# MCU.net
KiCad netlist of a schematic drawn in Altium Designer
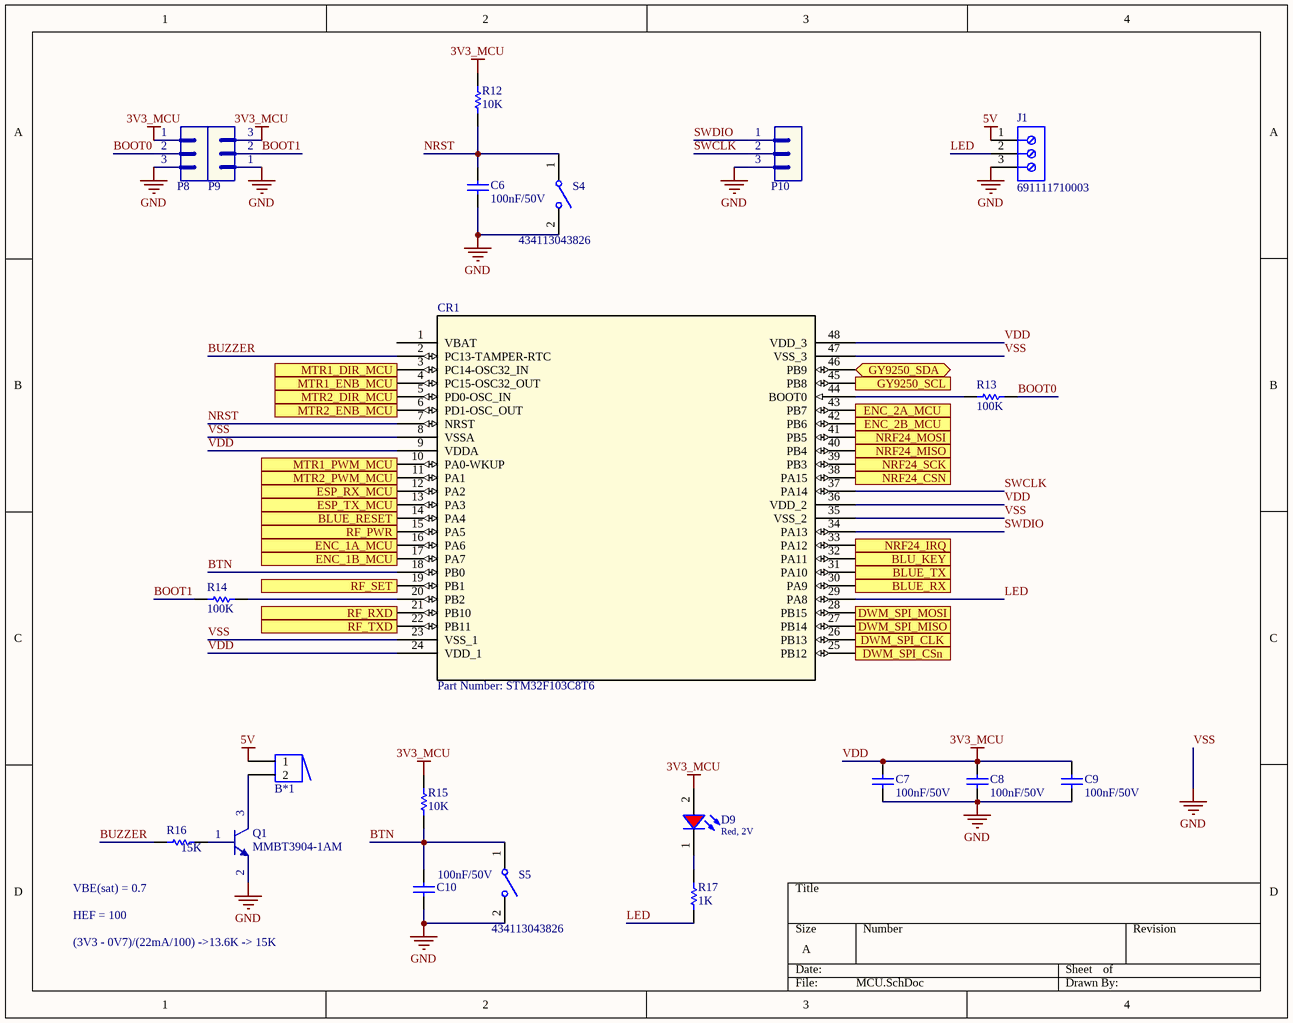
[diagram p0: MCU.SchDoc]

(export (version "E")
  (design (tool "Eeschema 10.0.6"))
  (components
    (comp (ref "B*1") (value "Buzzer") (footprint "BUZZER") (libsource (lib "chicken") (part "Buzzer")))
    (comp (ref "C6")
      (value "100nF/50V")
      (footprint "CAP-SM-0805")
      (description "CAP CER 0.1UF 50V Y5V 0805")
      (fields
        (field (name "MANUFACTURER") "Samsung Electro-Mechanics")
        (field (name "MANUFACTURER PART NUMBER") "CL21F104ZBCNNNC")
      )
      (libsource (lib "Capacitor") (part "Cap-100nF-50V-0805"))
    )
    (comp (ref "C7")
      (value "100nF/50V")
      (footprint "CAP-SM-0805")
      (description "CAP CER 0.1UF 50V Y5V 0805")
      (fields
        (field (name "MANUFACTURER") "Samsung Electro-Mechanics")
        (field (name "MANUFACTURER PART NUMBER") "CL21F104ZBCNNNC")
      )
      (libsource (lib "Capacitor") (part "Cap-100nF-50V-0805"))
    )
    (comp (ref "C8")
      (value "100nF/50V")
      (footprint "CAP-SM-0805")
      (description "CAP CER 0.1UF 50V Y5V 0805")
      (fields
        (field (name "MANUFACTURER") "Samsung Electro-Mechanics")
        (field (name "MANUFACTURER PART NUMBER") "CL21F104ZBCNNNC")
      )
      (libsource (lib "Capacitor") (part "Cap-100nF-50V-0805"))
    )
    (comp (ref "C9")
      (value "100nF/50V")
      (footprint "CAP-SM-0805")
      (description "CAP CER 0.1UF 50V Y5V 0805")
      (fields
        (field (name "MANUFACTURER") "Samsung Electro-Mechanics")
        (field (name "MANUFACTURER PART NUMBER") "CL21F104ZBCNNNC")
      )
      (libsource (lib "Capacitor") (part "Cap-100nF-50V-0805"))
    )
    (comp (ref "C10")
      (value "100nF/50V")
      (footprint "CAP-SM-0805")
      (description "CAP CER 0.1UF 50V Y5V 0805")
      (fields
        (field (name "MANUFACTURER") "Samsung Electro-Mechanics")
        (field (name "MANUFACTURER PART NUMBER") "CL21F104ZBCNNNC")
      )
      (libsource (lib "Capacitor") (part "Cap-100nF-50V-0805"))
    )
    (comp (ref "CR1")
      (value "Part Number: STM32F103C8T6")
      (footprint "LQFP-48")
      (description "No Description Available")
      (fields
        (field (name "MANUFACTURER_PART_NUMBER") "STM32F103C8T6")
        (field (name "COPYRIGHT") "Copyright (C) 2018 Accelerated Designs. All rights reserved")
      )
      (libsource (lib "chicken") (part "STM32F103C8T6"))
    )
    (comp (ref "D9")
      (value "Red, 2V")
      (footprint "WL-SMCW_0805")
      (description "WL-SMCW SMT Mono-color Chip LED Waterclear, size 0805, Red, 2V, 140deg")
      (fields (field (name "PART NUMBER") "150080RS75000") (field (name "PUBLISHER") "Wurth Elektronik"))
      (libsource (lib "150080BS75000_Altium_WL-SMCW_rev20a") (part "150080RS75000"))
    )
    (comp (ref "J1")
      (value "691111710003")
      (footprint "691111710003")
      (description "WR-TBL Serie 111 Horizontal Entry Modular, Pressure Clamp, pitch 5mm, 3p")
      (fields (field (name "PUBLISHER") "Wurth Elektronik"))
      (libsource (lib "o162719v243 Altium_WR-TBL (rev19a)") (part "691111710003"))
    )
    (comp (ref "P8")
      (value "Header 3")
      (footprint "JP3")
      (description "Header, 3-Pin")
      (fields (field (name "PUBLISHER") "Altium Limited"))
      (libsource (lib "Header-connector") (part "Header 3"))
    )
    (comp (ref "P9")
      (value "Header 3")
      (footprint "JP3")
      (description "Header, 3-Pin")
      (fields (field (name "PUBLISHER") "Altium Limited"))
      (libsource (lib "") (part "Header 3_1"))
    )
    (comp (ref "P10")
      (value "Header 3")
      (footprint "JP3")
      (description "Header, 3-Pin")
      (fields (field (name "PUBLISHER") "Altium Limited"))
      (libsource (lib "Header-connector") (part "Header 3"))
    )
    (comp (ref "Q1")
      (value "MMBT3904-1AM")
      (footprint "SOT23_NEX")
      (libsource (lib "BJT") (part "MMBT3904-1AM"))
    )
    (comp (ref "R12")
      (value "10K")
      (footprint "Resistor:RES-SM-0805")
      (description "RES 10K OHM 1% 1/4W 0805")
      (fields
        (field (name "MANUFACTURER") "Stackpole Electronics Inc")
        (field (name "MANUFACTURER PART NUMBER") "RNCP0805FTD10K0")
      )
      (libsource (lib "Resistor") (part "Res-10k-0805"))
    )
    (comp (ref "R13")
      (value "100K")
      (footprint "Resistor:RES-SM-0805")
      (description "RES 0 OHM JUMPER 0805")
      (fields
        (field (name "MANUFACTURER") "Vishay Dale")
        (field (name "MANUFACTURER PART NUMBER") "WSL080500000ZEA9")
      )
      (libsource (lib "Resistor") (part "Res-100K-0805"))
    )
    (comp (ref "R14")
      (value "100K")
      (footprint "Resistor:RES-SM-0805")
      (description "RES 0 OHM JUMPER 0805")
      (fields
        (field (name "MANUFACTURER") "Vishay Dale")
        (field (name "MANUFACTURER PART NUMBER") "WSL080500000ZEA9")
      )
      (libsource (lib "Resistor") (part "Res-100K-0805"))
    )
    (comp (ref "R15")
      (value "10K")
      (footprint "Resistor:RES-SM-0805")
      (description "RES 10K OHM 1% 1/4W 0805")
      (fields
        (field (name "MANUFACTURER") "Stackpole Electronics Inc")
        (field (name "MANUFACTURER PART NUMBER") "RNCP0805FTD10K0")
      )
      (libsource (lib "Resistor") (part "Res-10k-0805"))
    )
    (comp (ref "R16")
      (value "15K")
      (footprint "Resistor:RES-SM-0805")
      (description "RES 15K OHM 1% 1/4W 0805")
      (fields
        (field (name "MANUFACTURER") "TE Connectivity Passive Product")
        (field (name "MANUFACTURER PART NUMBER") "CRGCQ0805F15K")
      )
      (libsource (lib "Resistor") (part "Res-15K-0805"))
    )
    (comp (ref "R17")
      (value "1K")
      (footprint "Resistor:RES-SM-0805")
      (description "RES 1K OHM 1% 1/4W 0805")
      (fields
        (field (name "MANUFACTURER") "Stackpole Electronics Inc")
        (field (name "MANUFACTURER PART NUMBER") "RNCP0805FTD1K00")
      )
      (libsource (lib "Resistor") (part "Res-1K-0805"))
    )
    (comp (ref "S4")
      (value "434113043826")
      (footprint "434113043826")
      (description "WS-TASV J-Bend SMT Tact Switch 6x3.5mm, height 4.3mm, 260gf")
      (fields (field (name "PUBLISHER") "Wurth Elektronik"))
      (libsource (lib "434113043826_Altium_WS-TASV_rev20a") (part "434113043826"))
    )
    (comp (ref "S5")
      (value "434113043826")
      (footprint "434113043826")
      (description "WS-TASV J-Bend SMT Tact Switch 6x3.5mm, height 4.3mm, 260gf")
      (fields (field (name "PUBLISHER") "Wurth Elektronik"))
      (libsource (lib "434113043826_Altium_WS-TASV_rev20a") (part "434113043826"))
    )
  )
  (nets
    (net (code "1") (name "/BLUE_RESET") (class "Default")
      (node (ref "CR1") (pin "14") (pinfunction "PA4_14") (pintype "bidirectional"))
    )
    (net (code "2") (name "/BLUE_RX") (class "Default")
      (node (ref "CR1") (pin "30") (pinfunction "PA9_30") (pintype "bidirectional"))
    )
    (net (code "3") (name "/BLUE_TX") (class "Default")
      (node (ref "CR1") (pin "31") (pinfunction "PA10_31") (pintype "bidirectional"))
    )
    (net (code "4") (name "/BLU_KEY") (class "Default")
      (node (ref "CR1") (pin "32") (pinfunction "PA11_32") (pintype "bidirectional"))
    )
    (net (code "5") (name "/BOOT0") (class "Default")
      (node (ref "P8") (pin "2") (pinfunction "2_2") (pintype "passive"))
      (node (ref "R13") (pin "2") (pinfunction "2_2") (pintype "passive"))
    )
    (net (code "6") (name "/BOOT1") (class "Default")
      (node (ref "P9") (pin "2") (pinfunction "2_2") (pintype "passive"))
      (node (ref "R14") (pin "1") (pinfunction "1_1") (pintype "passive"))
    )
    (net (code "7") (name "/BTN") (class "Default")
      (node (ref "C10") (pin "2") (pinfunction "2_2") (pintype "passive"))
      (node (ref "CR1") (pin "18") (pinfunction "PB0_18") (pintype "bidirectional"))
      (node (ref "R15") (pin "1") (pinfunction "1_1") (pintype "passive"))
      (node (ref "S5") (pin "1") (pinfunction "1_1") (pintype "passive"))
    )
    (net (code "8") (name "/BUZZER") (class "Default")
      (node (ref "CR1") (pin "2") (pinfunction "PC13-TAMPER-RTC_2") (pintype "bidirectional"))
      (node (ref "R16") (pin "1") (pinfunction "1_1") (pintype "passive"))
    )
    (net (code "9") (name "/DWM_SPI_CLK") (class "Default")
      (node (ref "CR1") (pin "26") (pinfunction "PB13_26") (pintype "bidirectional"))
    )
    (net (code "10") (name "/DWM_SPI_CSn") (class "Default")
      (node (ref "CR1") (pin "25") (pinfunction "PB12_25") (pintype "bidirectional"))
    )
    (net (code "11") (name "/DWM_SPI_MISO") (class "Default")
      (node (ref "CR1") (pin "27") (pinfunction "PB14_27") (pintype "bidirectional"))
    )
    (net (code "12") (name "/DWM_SPI_MOSI") (class "Default")
      (node (ref "CR1") (pin "28") (pinfunction "PB15_28") (pintype "bidirectional"))
    )
    (net (code "13") (name "/ENC_1A_MCU") (class "Default")
      (node (ref "CR1") (pin "16") (pinfunction "PA6_16") (pintype "bidirectional"))
    )
    (net (code "14") (name "/ENC_1B_MCU") (class "Default")
      (node (ref "CR1") (pin "17") (pinfunction "PA7_17") (pintype "bidirectional"))
    )
    (net (code "15") (name "/ENC_2A_MCU") (class "Default")
      (node (ref "CR1") (pin "43") (pinfunction "PB7_43") (pintype "bidirectional"))
    )
    (net (code "16") (name "/ENC_2B_MCU") (class "Default")
      (node (ref "CR1") (pin "42") (pinfunction "PB6_42") (pintype "bidirectional"))
    )
    (net (code "17") (name "/ESP_RX_MCU") (class "Default")
      (node (ref "CR1") (pin "12") (pinfunction "PA2_12") (pintype "bidirectional"))
    )
    (net (code "18") (name "/ESP_TX_MCU") (class "Default")
      (node (ref "CR1") (pin "13") (pinfunction "PA3_13") (pintype "bidirectional"))
    )
    (net (code "19") (name "/GY9250_SCL") (class "Default")
      (node (ref "CR1") (pin "45") (pinfunction "PB8_45") (pintype "bidirectional"))
    )
    (net (code "20") (name "/GY9250_SDA") (class "Default")
      (node (ref "CR1") (pin "46") (pinfunction "PB9_46") (pintype "bidirectional"))
    )
    (net (code "21") (name "/LED") (class "Default")
      (node (ref "CR1") (pin "29") (pinfunction "PA8_29") (pintype "bidirectional"))
      (node (ref "J1") (pin "2") (pinfunction "2_2") (pintype "passive"))
      (node (ref "R17") (pin "1") (pinfunction "1_1") (pintype "passive"))
    )
    (net (code "22") (name "/MTR1_DIR_MCU") (class "Default")
      (node (ref "CR1") (pin "3") (pinfunction "PC14-OSC32_IN_3") (pintype "bidirectional"))
    )
    (net (code "23") (name "/MTR1_ENB_MCU") (class "Default")
      (node (ref "CR1") (pin "4") (pinfunction "PC15-OSC32_OUT_4") (pintype "bidirectional"))
    )
    (net (code "24") (name "/MTR1_PWM_MCU") (class "Default")
      (node (ref "CR1") (pin "10") (pinfunction "PA0-WKUP_10") (pintype "bidirectional"))
    )
    (net (code "25") (name "/MTR2_DIR_MCU") (class "Default")
      (node (ref "CR1") (pin "5") (pinfunction "PD0-OSC_IN_5") (pintype "bidirectional"))
    )
    (net (code "26") (name "/MTR2_ENB_MCU") (class "Default")
      (node (ref "CR1") (pin "6") (pinfunction "PD1-OSC_OUT_6") (pintype "bidirectional"))
    )
    (net (code "27") (name "/MTR2_PWM_MCU") (class "Default")
      (node (ref "CR1") (pin "11") (pinfunction "PA1_11") (pintype "bidirectional"))
    )
    (net (code "28") (name "/NRF24_CSN") (class "Default")
      (node (ref "CR1") (pin "38") (pinfunction "PA15_38") (pintype "bidirectional"))
    )
    (net (code "29") (name "/NRF24_IRQ") (class "Default")
      (node (ref "CR1") (pin "33") (pinfunction "PA12_33") (pintype "bidirectional"))
    )
    (net (code "30") (name "/NRF24_MISO") (class "Default")
      (node (ref "CR1") (pin "40") (pinfunction "PB4_40") (pintype "bidirectional"))
    )
    (net (code "31") (name "/NRF24_MOSI") (class "Default")
      (node (ref "CR1") (pin "41") (pinfunction "PB5_41") (pintype "bidirectional"))
    )
    (net (code "32") (name "/NRF24_SCK") (class "Default")
      (node (ref "CR1") (pin "39") (pinfunction "PB3_39") (pintype "bidirectional"))
    )
    (net (code "33") (name "/NRST") (class "Default")
      (node (ref "C6") (pin "2") (pinfunction "2_2") (pintype "passive"))
      (node (ref "CR1") (pin "7") (pinfunction "NRST_7") (pintype "bidirectional"))
      (node (ref "R12") (pin "1") (pinfunction "1_1") (pintype "passive"))
      (node (ref "S4") (pin "1") (pinfunction "1_1") (pintype "passive"))
    )
    (net (code "34") (name "/RF_PWR") (class "Default")
      (node (ref "CR1") (pin "15") (pinfunction "PA5_15") (pintype "bidirectional"))
    )
    (net (code "35") (name "/RF_RXD") (class "Default")
      (node (ref "CR1") (pin "21") (pinfunction "PB10_21") (pintype "bidirectional"))
    )
    (net (code "36") (name "/RF_SET") (class "Default")
      (node (ref "CR1") (pin "19") (pinfunction "PB1_19") (pintype "bidirectional"))
    )
    (net (code "37") (name "/RF_TXD") (class "Default")
      (node (ref "CR1") (pin "22") (pinfunction "PB11_22") (pintype "bidirectional"))
    )
    (net (code "38") (name "/SWCLK") (class "Default")
      (node (ref "CR1") (pin "37") (pinfunction "PA14_37") (pintype "bidirectional"))
      (node (ref "P10") (pin "2") (pinfunction "2_2") (pintype "passive"))
    )
    (net (code "39") (name "/SWDIO") (class "Default")
      (node (ref "CR1") (pin "34") (pinfunction "PA13_34") (pintype "bidirectional"))
      (node (ref "P10") (pin "1") (pinfunction "1_1") (pintype "passive"))
    )
    (net (code "40") (name "3V3_MCU") (class "Default")
      (node (ref "C7") (pin "2") (pinfunction "2_2") (pintype "passive"))
      (node (ref "C8") (pin "1") (pinfunction "1_1") (pintype "passive"))
      (node (ref "C9") (pin "1") (pinfunction "1_1") (pintype "passive"))
      (node (ref "CR1") (pin "24") (pinfunction "VDD_1_24") (pintype "power_in"))
      (node (ref "CR1") (pin "36") (pinfunction "VDD_2_36") (pintype "power_in"))
      (node (ref "CR1") (pin "48") (pinfunction "VDD_3_48") (pintype "power_in"))
      (node (ref "CR1") (pin "9") (pinfunction "VDDA_9") (pintype "power_in"))
      (node (ref "D9") (pin "2") (pinfunction "A_2") (pintype "passive"))
      (node (ref "P8") (pin "1") (pinfunction "1_1") (pintype "passive"))
      (node (ref "P9") (pin "3") (pinfunction "3_3") (pintype "passive"))
      (node (ref "R12") (pin "2") (pinfunction "2_2") (pintype "passive"))
      (node (ref "R15") (pin "2") (pinfunction "2_2") (pintype "passive"))
    )
    (net (code "41") (name "5V") (class "Default")
      (node (ref "B*1") (pin "1") (pinfunction "1_1") (pintype "passive"))
      (node (ref "J1") (pin "1") (pinfunction "1_1") (pintype "passive"))
    )
    (net (code "42") (name "GND") (class "Default")
      (node (ref "C10") (pin "1") (pinfunction "1_1") (pintype "passive"))
      (node (ref "C6") (pin "1") (pinfunction "1_1") (pintype "passive"))
      (node (ref "C7") (pin "1") (pinfunction "1_1") (pintype "passive"))
      (node (ref "C8") (pin "2") (pinfunction "2_2") (pintype "passive"))
      (node (ref "C9") (pin "2") (pinfunction "2_2") (pintype "passive"))
      (node (ref "CR1") (pin "23") (pinfunction "VSS_1_23") (pintype "power_in"))
      (node (ref "CR1") (pin "35") (pinfunction "VSS_2_35") (pintype "power_in"))
      (node (ref "CR1") (pin "47") (pinfunction "VSS_3_47") (pintype "power_in"))
      (node (ref "CR1") (pin "8") (pinfunction "VSSA_8") (pintype "power_in"))
      (node (ref "J1") (pin "3") (pinfunction "3_3") (pintype "passive"))
      (node (ref "P10") (pin "3") (pinfunction "3_3") (pintype "passive"))
      (node (ref "P8") (pin "3") (pinfunction "3_3") (pintype "passive"))
      (node (ref "P9") (pin "1") (pinfunction "1_1") (pintype "passive"))
      (node (ref "Q1") (pin "2") (pinfunction "E_2") (pintype "passive"))
      (node (ref "S4") (pin "2") (pinfunction "2_2") (pintype "passive"))
      (node (ref "S5") (pin "2") (pinfunction "2_2") (pintype "passive"))
    )
    (net (code "43") (name "Net-(CR1-BOOT0)") (class "Default")
      (node (ref "CR1") (pin "44") (pinfunction "BOOT0_44") (pintype "input"))
      (node (ref "R13") (pin "1") (pinfunction "1_1") (pintype "passive"))
    )
    (net (code "44") (name "Net-(CR1-PB2)") (class "Default")
      (node (ref "CR1") (pin "20") (pinfunction "PB2_20") (pintype "bidirectional"))
      (node (ref "R14") (pin "2") (pinfunction "2_2") (pintype "passive"))
    )
    (net (code "45") (name "Net-(D9-K)") (class "Default")
      (node (ref "D9") (pin "1") (pinfunction "K_1") (pintype "passive"))
      (node (ref "R17") (pin "2") (pinfunction "2_2") (pintype "passive"))
    )
    (net (code "46") (name "Net-(Q1-B)") (class "Default")
      (node (ref "Q1") (pin "1") (pinfunction "B_1") (pintype "passive"))
      (node (ref "R16") (pin "2") (pinfunction "2_2") (pintype "passive"))
    )
    (net (code "47") (name "Net-(Q1-C)") (class "Default")
      (node (ref "B*1") (pin "2") (pinfunction "2_2") (pintype "passive"))
      (node (ref "Q1") (pin "3") (pinfunction "C_3") (pintype "passive"))
    )
    (net (code "48") (name "unconnected-(CR1-VBAT-Pad1)") (class "Default")
      (node (ref "CR1") (pin "1") (pinfunction "VBAT_1") (pintype "power_in"))
    )
  )
)
